# linea_base_2.net
KiCad netlist of a schematic drawn in EAGLE
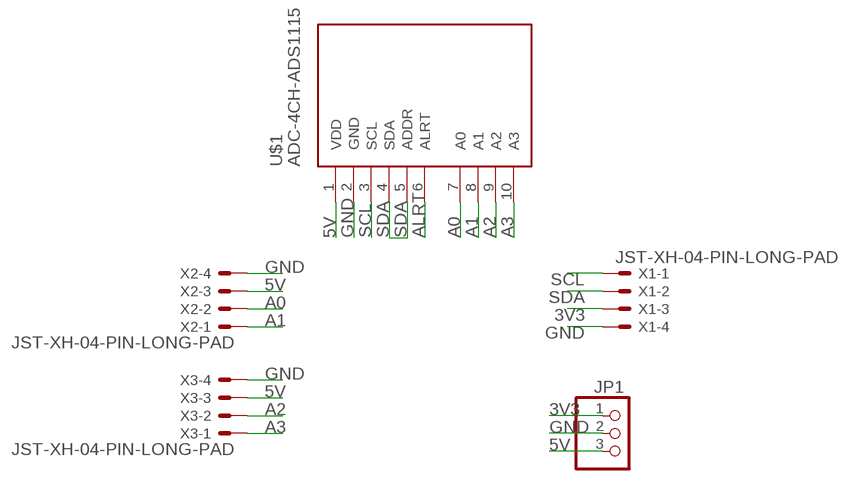
[diagram p0: schematic, sheet 1]

(export (version "E")
  (design (tool "Eeschema 10.0.6"))
  (components
    (comp (ref "JP1")
      (value "PINHD-1X3")
      (footprint "eagle-import:1X03")
      (libsource (lib "eagle-import") (part "PINHD-1X3"))
    )
    (comp (ref "U$1")
      (value "ADC-4CH-ADS1115")
      (footprint "eagle-import:ADC-4CH-ADS1115")
      (libsource (lib "eagle-import") (part "ADC-4CH-ADS1115"))
    )
    (comp (ref "X1")
      (value "JST-XH-04-PIN-LONG-PAD")
      (footprint "eagle-import:JST-XH-04-PACKAGE-LONG-PAD")
      (libsource (lib "eagle-import") (part "JST-XH-04-PIN-LONG-PAD"))
    )
    (comp (ref "X2")
      (value "JST-XH-04-PIN-LONG-PAD")
      (footprint "eagle-import:JST-XH-04-PACKAGE-LONG-PAD")
      (libsource (lib "eagle-import") (part "JST-XH-04-PIN-LONG-PAD"))
    )
    (comp (ref "X3")
      (value "JST-XH-04-PIN-LONG-PAD")
      (footprint "eagle-import:JST-XH-04-PACKAGE-LONG-PAD")
      (libsource (lib "eagle-import") (part "JST-XH-04-PIN-LONG-PAD"))
    )
  )
  (nets
    (net (code "1") (name "/3V3") (class "Default")
      (node (ref "JP1") (pin "1") (pinfunction "1_1") (pintype "passive"))
      (node (ref "X1") (pin "3") (pinfunction "S_3") (pintype "passive"))
    )
    (net (code "2") (name "/5V") (class "Default")
      (node (ref "JP1") (pin "3") (pinfunction "3_3") (pintype "passive"))
      (node (ref "U$1") (pin "1") (pinfunction "VDD_1") (pintype "power_in"))
      (node (ref "X2") (pin "3") (pinfunction "S_3") (pintype "passive"))
      (node (ref "X3") (pin "3") (pinfunction "S_3") (pintype "passive"))
    )
    (net (code "3") (name "/A0") (class "Default")
      (node (ref "U$1") (pin "7") (pinfunction "A0_7") (pintype "input"))
      (node (ref "X2") (pin "2") (pinfunction "S_2") (pintype "passive"))
    )
    (net (code "4") (name "/A1") (class "Default")
      (node (ref "U$1") (pin "8") (pinfunction "A1_8") (pintype "input"))
      (node (ref "X2") (pin "1") (pinfunction "S_1") (pintype "passive"))
    )
    (net (code "5") (name "/A2") (class "Default")
      (node (ref "U$1") (pin "9") (pinfunction "A2_9") (pintype "input"))
      (node (ref "X3") (pin "2") (pinfunction "S_2") (pintype "passive"))
    )
    (net (code "6") (name "/A3") (class "Default")
      (node (ref "U$1") (pin "10") (pinfunction "A3_10") (pintype "input"))
      (node (ref "X3") (pin "1") (pinfunction "S_1") (pintype "passive"))
    )
    (net (code "7") (name "/ALRT") (class "Default")
      (node (ref "U$1") (pin "6") (pinfunction "ALRT_6") (pintype "bidirectional"))
    )
    (net (code "8") (name "/GND") (class "Default")
      (node (ref "JP1") (pin "2") (pinfunction "2_2") (pintype "passive"))
      (node (ref "U$1") (pin "2") (pinfunction "GND_2") (pintype "power_in"))
      (node (ref "X1") (pin "4") (pinfunction "S_4") (pintype "passive"))
      (node (ref "X2") (pin "4") (pinfunction "S_4") (pintype "passive"))
      (node (ref "X3") (pin "4") (pinfunction "S_4") (pintype "passive"))
    )
    (net (code "9") (name "/SCL") (class "Default")
      (node (ref "U$1") (pin "3") (pinfunction "SCL_3") (pintype "bidirectional"))
      (node (ref "X1") (pin "1") (pinfunction "S_1") (pintype "passive"))
    )
    (net (code "10") (name "/SDA") (class "Default")
      (node (ref "U$1") (pin "4") (pinfunction "SDA_4") (pintype "bidirectional"))
      (node (ref "U$1") (pin "5") (pinfunction "ADDR_5") (pintype "bidirectional"))
      (node (ref "X1") (pin "2") (pinfunction "S_2") (pintype "passive"))
    )
  )
)
